# I2C-Motion-sensor.net
KiCad netlist of a schematic drawn in Altium Designer
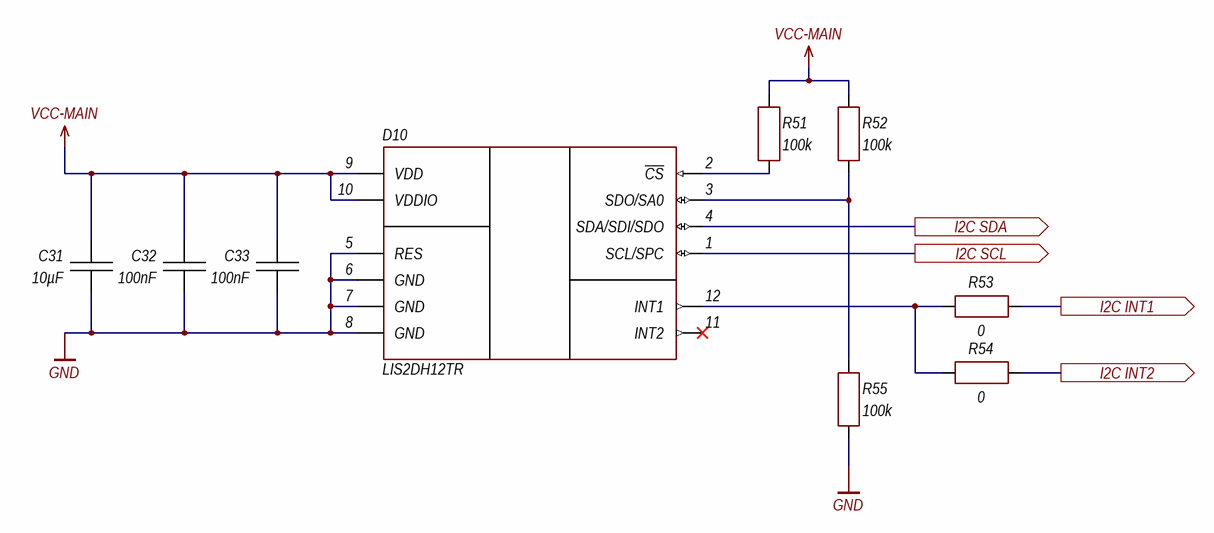
[diagram p0: I2C-Motion-sensor.SchDoc]

(export (version "E")
  (design (tool "Eeschema 10.0.6"))
  (components
    (comp (ref "C31") (value "10µF") (footprint "CH0402C") (libsource (lib "Discrete") (part "Capacitor")))
    (comp (ref "C32") (value "100nF") (footprint "CH0402C") (libsource (lib "Discrete") (part "Capacitor")))
    (comp (ref "C33") (value "100nF") (footprint "CH0402C") (libsource (lib "Discrete") (part "Capacitor")))
    (comp (ref "D10")
      (value "LIS2DH12TR")
      (footprint "12-LGA (2x2mm)")
      (description "Motion sensor, I2C")
      (fields (field (name "MANUFACTURER") "STMicroelectronics"))
      (libsource (lib "Digital") (part "LIS2DH12TR"))
    )
    (comp (ref "R51") (value "100k") (footprint "CH0402R") (libsource (lib "Discrete") (part "Resistor")))
    (comp (ref "R52") (value "100k") (footprint "CH0402R") (libsource (lib "Discrete") (part "Resistor")))
    (comp (ref "R53") (value "0") (footprint "CH0402R") (libsource (lib "") (part "Resistor_1")))
    (comp (ref "R54") (value "0") (footprint "CH0402R") (libsource (lib "") (part "Resistor_1")))
    (comp (ref "R55") (value "100k") (footprint "CH0402R") (libsource (lib "Discrete") (part "Resistor")))
  )
  (nets
    (net (code "1") (name "/I2C INT1") (class "Default")
      (node (ref "R53") (pin "1") (pinfunction "1_1") (pintype "passive"))
    )
    (net (code "2") (name "/I2C INT2") (class "Default")
      (node (ref "R54") (pin "1") (pinfunction "1_1") (pintype "passive"))
    )
    (net (code "3") (name "/I2C SCL") (class "Default")
      (node (ref "D10") (pin "1") (pinfunction "SCL/SPC_1") (pintype "bidirectional"))
    )
    (net (code "4") (name "/I2C SDA") (class "Default")
      (node (ref "D10") (pin "4") (pinfunction "SDA/SDI/SDO_4") (pintype "bidirectional"))
    )
    (net (code "5") (name "GND") (class "Default")
      (node (ref "C31") (pin "1") (pinfunction "1_1") (pintype "passive"))
      (node (ref "C32") (pin "1") (pinfunction "1_1") (pintype "passive"))
      (node (ref "C33") (pin "1") (pinfunction "1_1") (pintype "passive"))
      (node (ref "D10") (pin "5") (pinfunction "RES_5") (pintype "passive"))
      (node (ref "D10") (pin "6") (pinfunction "GND_6") (pintype "power_in"))
      (node (ref "D10") (pin "7") (pinfunction "GND_7") (pintype "power_in"))
      (node (ref "D10") (pin "8") (pinfunction "GND_8") (pintype "power_in"))
      (node (ref "R55") (pin "1") (pinfunction "1_1") (pintype "passive"))
    )
    (net (code "6") (name "Net-(D10-INT1)") (class "Default")
      (node (ref "D10") (pin "12") (pinfunction "INT1_12") (pintype "output"))
      (node (ref "R53") (pin "2") (pinfunction "2_2") (pintype "passive"))
      (node (ref "R54") (pin "2") (pinfunction "2_2") (pintype "passive"))
    )
    (net (code "7") (name "Net-(D10-SDO{slash}SA0)") (class "Default")
      (node (ref "D10") (pin "3") (pinfunction "SDO/SA0_3") (pintype "bidirectional"))
      (node (ref "R52") (pin "1") (pinfunction "1_1") (pintype "passive"))
      (node (ref "R55") (pin "2") (pinfunction "2_2") (pintype "passive"))
    )
    (net (code "8") (name "Net-(D10-~{CS})") (class "Default")
      (node (ref "D10") (pin "2") (pinfunction "~{CS}_2") (pintype "input"))
      (node (ref "R51") (pin "1") (pinfunction "1_1") (pintype "passive"))
    )
    (net (code "9") (name "VCC-MAIN") (class "Default")
      (node (ref "C31") (pin "2") (pinfunction "2_2") (pintype "passive"))
      (node (ref "C32") (pin "2") (pinfunction "2_2") (pintype "passive"))
      (node (ref "C33") (pin "2") (pinfunction "2_2") (pintype "passive"))
      (node (ref "D10") (pin "10") (pinfunction "VDDIO_10") (pintype "power_in"))
      (node (ref "D10") (pin "9") (pinfunction "VDD_9") (pintype "power_in"))
      (node (ref "R51") (pin "2") (pinfunction "2_2") (pintype "passive"))
      (node (ref "R52") (pin "2") (pinfunction "2_2") (pintype "passive"))
    )
    (net (code "10") (name "unconnected-(D10-INT2-Pad11)") (class "Default")
      (node (ref "D10") (pin "11") (pinfunction "INT2_11") (pintype "output+no_connect"))
    )
  )
)
